# Power.net
KiCad netlist of a schematic drawn in Altium Designer
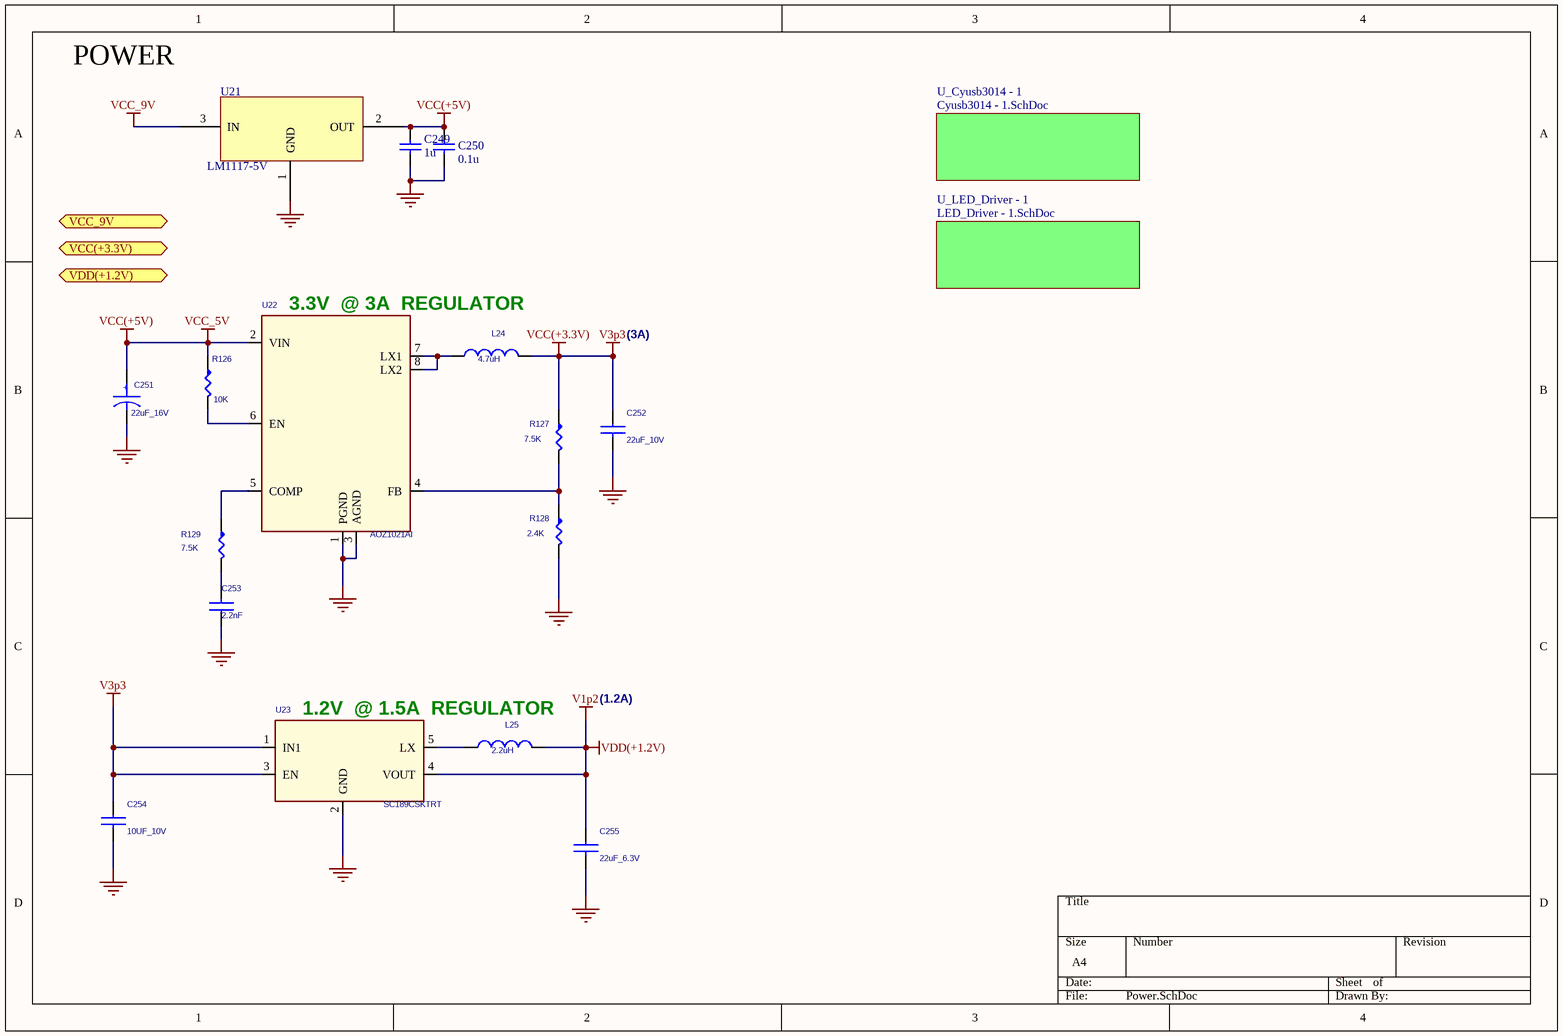
[diagram p0: Power.SchDoc]

(export (version "E")
  (design (tool "Eeschema 10.0.6"))
  (components
    (comp (ref "C249")
      (value "1u")
      (footprint "C0603")
      (description "50V/8.2u/0805")
      (fields (field (name "PUBLISHER") "Altium Limited"))
      (libsource (lib "Miscellaneous Devices") (part "Cap"))
    )
    (comp (ref "C250")
      (value "0.1u")
      (footprint "C0603")
      (description "Capacitor")
      (fields (field (name "PUBLISHER") "Altium Limited"))
      (libsource (lib "WM360") (part "CAP0805"))
    )
    (comp (ref "C251")
      (value "22uF_16V")
      (description "CAP TANT 22UF 16V 10% 1206")
      (fields (field (name "MANUFACTURER") "Nichicon") (field (name "PART NUMBER") "F951C226KQAAQ2"))
      (libsource (lib "*") (part "CAP POL"))
    )
    (comp (ref "C252") (value "22uF_10V") (libsource (lib "*") (part "CAPACITOR NON-POL")))
    (comp (ref "C253")
      (value "2.2nF")
      (description "CAP CER 2200PF 50V 10% X7R 0805")
      (fields (field (name "MANUFACTURER") "Yageo") (field (name "PART NUMBER") "CC0805KRX7R9BB222"))
      (libsource (lib "*") (part "CAPACITOR NON-POL"))
    )
    (comp (ref "C254")
      (value "10UF_10V")
      (footprint "CAPC2012X145M")
      (libsource (lib "*") (part "CAPACITOR NON-POL"))
    )
    (comp (ref "C255") (value "22uF_6.3V") (libsource (lib "*") (part "CAPACITOR NON-POL")))
    (comp (ref "L24")
      (value "4.7uH")
      (description "INDUCTOR 4.7UH 2.7A 20% SMD")
      (fields (field (name "PART NUMBER") "NR6028T4R7M") (field (name "MANUFACTURER") "Taiyo Yuden"))
      (libsource (lib "*") (part "INDUCTOR"))
    )
    (comp (ref "L25")
      (value "2.2uH")
      (description "INDUCTOR 2.2UH 1.20A 20% 1210")
      (fields (field (name "PART NUMBER") "NLCV32T-2R2M-PFR") (field (name "MANUFACTURER") "TDK Corporation"))
      (libsource (lib "*") (part "INDUCTOR"))
    )
    (comp (ref "R126")
      (value "10K")
      (footprint "RESC1608X55M")
      (description "RES 10.0K OHM 1/10W 1% 0603 SMD")
      (fields (field (name "MANUFACTURER") "Panasonic - ECG") (field (name "PART NUMBER") "ERJ-3EKF1002V"))
      (libsource (lib "*") (part "R_Dup1"))
    )
    (comp (ref "R127")
      (value "7.5K")
      (footprint "RESC1608X55M")
      (description "RES 7.5K OHM 1/10W 1% 0603 SMD")
      (fields (field (name "MANUFACTURER") "Panasonic - ECG") (field (name "PART NUMBER") "ERJ-3EKF7501V"))
      (libsource (lib "*") (part "R_Dup1"))
    )
    (comp (ref "R128")
      (value "2.4K")
      (footprint "RESC1608X55M")
      (description "RES 2.4K OHM 1/10W 1% 0603 SMD")
      (fields (field (name "MANUFACTURER") "Panasonic - ECG") (field (name "PART NUMBER") "ERJ-3EKF2401V"))
      (libsource (lib "*") (part "R_Dup1"))
    )
    (comp (ref "R129")
      (value "7.5K")
      (footprint "RESC1608X55M")
      (description "RES 7.5K OHM 1/10W 1% 0603 SMD")
      (fields (field (name "PART NUMBER") "ERJ-3EKF7501V") (field (name "MANUFACTURER") "Panasonic - ECG"))
      (libsource (lib "*") (part "R_Dup1"))
    )
    (comp (ref "U21") (value "LM1117-5V") (footprint "SOT-223") (libsource (lib "rs232") (part "AMS1117")))
    (comp (ref "U22")
      (value "AOZ1021AI")
      (footprint "SOIC127P600X175-8M")
      (description "IC REG BUCK SYNC ADJ 3A 8SOIC")
      (fields (field (name "MANUFACTURER") "Alpha & Omega Semiconductor Inc"))
      (libsource (lib "*") (part "AOZ1021AI"))
    )
    (comp (ref "U23")
      (value "SC189CSKTRT")
      (footprint "SOT95P280X145-5M")
      (description "IC REG BUCK SYNC 1.2V SOT23-5")
      (fields (field (name "MANUFACTURER") "Semtech"))
      (libsource (lib "*") (part "SC189CSKTRT"))
    )
  )
  (nets
    (net (code "1") (name "GND") (class "Default")
      (node (ref "C249") (pin "1") (pinfunction "1_1") (pintype "passive"))
      (node (ref "C250") (pin "2") (pinfunction "2_2") (pintype "passive"))
      (node (ref "C251") (pin "2") (pinfunction "2_2") (pintype "passive"))
      (node (ref "C252") (pin "2") (pinfunction "2_2") (pintype "passive"))
      (node (ref "C253") (pin "1") (pinfunction "1_1") (pintype "passive"))
      (node (ref "C254") (pin "2") (pinfunction "2_2") (pintype "passive"))
      (node (ref "C255") (pin "2") (pinfunction "2_2") (pintype "passive"))
      (node (ref "R128") (pin "2") (pinfunction "2_2") (pintype "passive"))
      (node (ref "U21") (pin "1") (pinfunction "GND_1") (pintype "passive"))
      (node (ref "U22") (pin "1") (pinfunction "PGND_1") (pintype "passive"))
      (node (ref "U22") (pin "3") (pinfunction "AGND_3") (pintype "passive"))
      (node (ref "U23") (pin "2") (pinfunction "GND_2") (pintype "passive"))
    )
    (net (code "2") (name "Net-(C253-Pad2)") (class "Default")
      (node (ref "C253") (pin "2") (pinfunction "2_2") (pintype "passive"))
      (node (ref "R129") (pin "2") (pinfunction "2_2") (pintype "passive"))
    )
    (net (code "3") (name "Net-(U22-COMP)") (class "Default")
      (node (ref "R129") (pin "1") (pinfunction "1_1") (pintype "passive"))
      (node (ref "U22") (pin "5") (pinfunction "COMP_5") (pintype "passive"))
    )
    (net (code "4") (name "Net-(U22-EN)") (class "Default")
      (node (ref "R126") (pin "2") (pinfunction "2_2") (pintype "passive"))
      (node (ref "U22") (pin "6") (pinfunction "EN_6") (pintype "passive"))
    )
    (net (code "5") (name "Net-(U22-FB)") (class "Default")
      (node (ref "R127") (pin "2") (pinfunction "2_2") (pintype "passive"))
      (node (ref "R128") (pin "1") (pinfunction "1_1") (pintype "passive"))
      (node (ref "U22") (pin "4") (pinfunction "FB_4") (pintype "passive"))
    )
    (net (code "6") (name "Net-(U22-LX1)") (class "Default")
      (node (ref "L24") (pin "1") (pinfunction "1_1") (pintype "passive"))
      (node (ref "U22") (pin "7") (pinfunction "LX1_7") (pintype "passive"))
      (node (ref "U22") (pin "8") (pinfunction "LX2_8") (pintype "passive"))
    )
    (net (code "7") (name "Net-(U23-LX)") (class "Default")
      (node (ref "L25") (pin "1") (pinfunction "1_1") (pintype "passive"))
      (node (ref "U23") (pin "5") (pinfunction "LX_5") (pintype "passive"))
    )
    (net (code "8") (name "V1p2") (class "Default")
      (node (ref "C255") (pin "1") (pinfunction "1_1") (pintype "passive"))
      (node (ref "L25") (pin "2") (pinfunction "2_2") (pintype "passive"))
      (node (ref "U23") (pin "4") (pinfunction "VOUT_4") (pintype "passive"))
    )
    (net (code "9") (name "V3p3") (class "Default")
      (node (ref "C252") (pin "1") (pinfunction "1_1") (pintype "passive"))
      (node (ref "C254") (pin "1") (pinfunction "1_1") (pintype "passive"))
      (node (ref "L24") (pin "2") (pinfunction "2_2") (pintype "passive"))
      (node (ref "R127") (pin "1") (pinfunction "1_1") (pintype "passive"))
      (node (ref "U23") (pin "1") (pinfunction "IN1_1") (pintype "passive"))
      (node (ref "U23") (pin "3") (pinfunction "EN_3") (pintype "passive"))
    )
    (net (code "10") (name "VCC(+5V)") (class "Default")
      (node (ref "C249") (pin "2") (pinfunction "2_2") (pintype "passive"))
      (node (ref "C250") (pin "1") (pinfunction "1_1") (pintype "passive"))
      (node (ref "C251") (pin "1") (pinfunction "1_1") (pintype "passive"))
      (node (ref "R126") (pin "1") (pinfunction "1_1") (pintype "passive"))
      (node (ref "U21") (pin "2") (pinfunction "OUT_2") (pintype "passive"))
      (node (ref "U22") (pin "2") (pinfunction "VIN_2") (pintype "passive"))
    )
    (net (code "11") (name "VCC_9V") (class "Default")
      (node (ref "U21") (pin "3") (pinfunction "IN_3") (pintype "passive"))
    )
  )
)
